# object_1.net
KiCad netlist of a schematic drawn in EAGLE
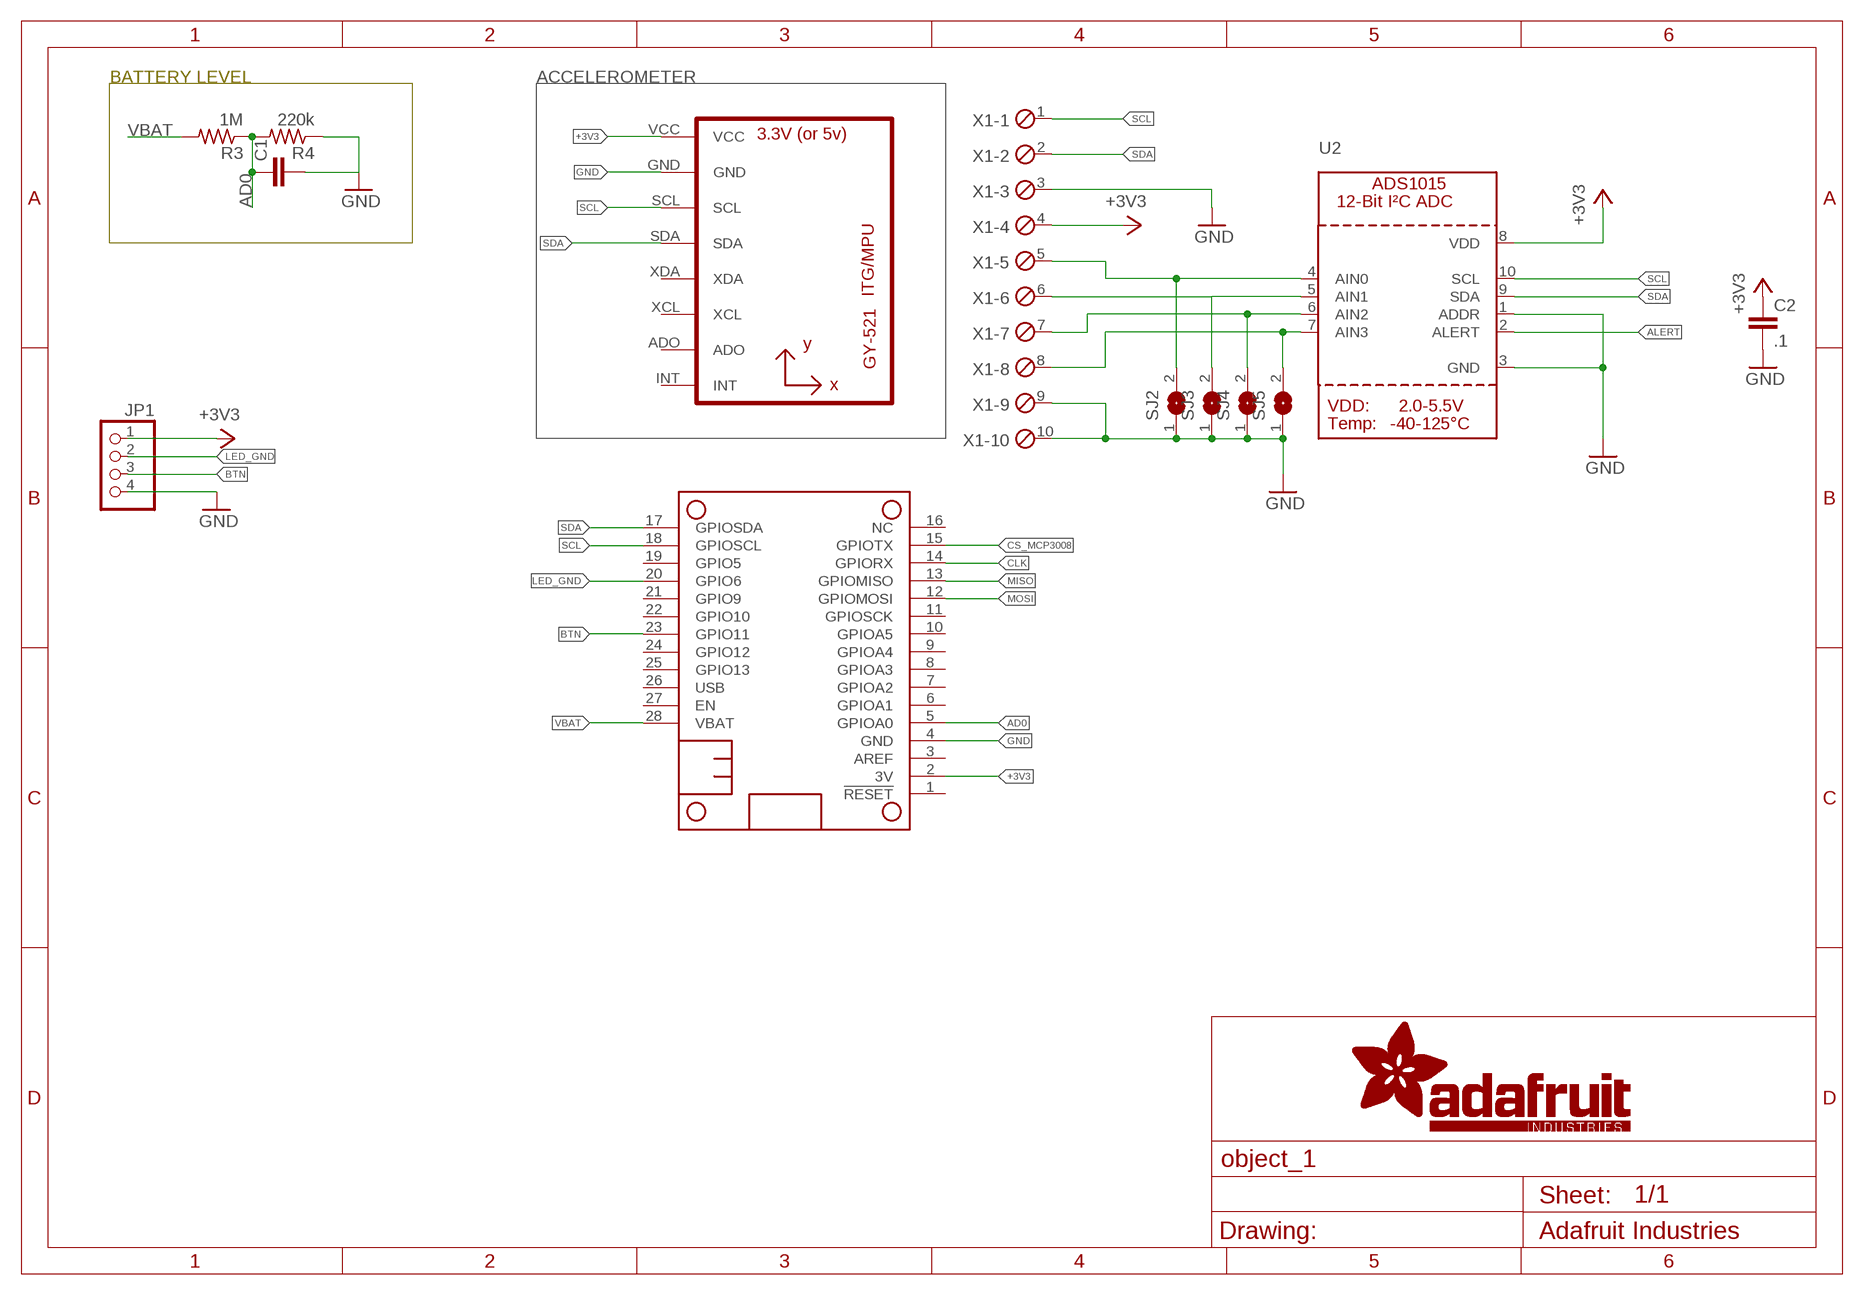
[diagram p0: schematic, sheet 1]

(export (version "E")
  (design (tool "Eeschema 10.0.6"))
  (components
    (comp (ref "C1")
      (value "C-EUC0805K")
      (footprint "eagle-import:C0805K")
      (libsource (lib "eagle-import") (part "C-EUC0805K"))
    )
    (comp (ref "C2")
      (value ".1")
      (footprint "eagle-import:C0805K")
      (libsource (lib "eagle-import") (part "C-EUC0805K"))
    )
    (comp (ref "JP1")
      (value "PINHD-1X4/90")
      (footprint "eagle-import:1X04_90")
      (libsource (lib "eagle-import") (part "PINHD-1X4/90"))
    )
    (comp (ref "MS1")
      (value "FEATHERWING_NODIM")
      (footprint "eagle-import:FEATHERWING_DIM")
      (libsource (lib "eagle-import") (part "FEATHERWING_NODIM"))
    )
    (comp (ref "R3")
      (value "1M")
      (footprint "eagle-import:M0805")
      (libsource (lib "eagle-import") (part "R-US_M0805"))
    )
    (comp (ref "R4")
      (value "220k")
      (footprint "eagle-import:M0805")
      (libsource (lib "eagle-import") (part "R-US_M0805"))
    )
    (comp (ref "SJ2")
      (value "SOLDERJUMPER")
      (footprint "eagle-import:SOLDERJUMPER_ARROW_NOPASTE")
      (libsource (lib "eagle-import") (part "SOLDERJUMPER"))
    )
    (comp (ref "SJ3")
      (value "SOLDERJUMPER")
      (footprint "eagle-import:SOLDERJUMPER_ARROW_NOPASTE")
      (libsource (lib "eagle-import") (part "SOLDERJUMPER"))
    )
    (comp (ref "SJ4")
      (value "SOLDERJUMPER")
      (footprint "eagle-import:SOLDERJUMPER_ARROW_NOPASTE")
      (libsource (lib "eagle-import") (part "SOLDERJUMPER"))
    )
    (comp (ref "SJ5")
      (value "SOLDERJUMPER")
      (footprint "eagle-import:SOLDERJUMPER_ARROW_NOPASTE")
      (libsource (lib "eagle-import") (part "SOLDERJUMPER"))
    )
    (comp (ref "U1")
      (value "GY-521MPU6050")
      (footprint "eagle-import:GY-521")
      (libsource (lib "eagle-import") (part "GY-521MPU6050"))
    )
    (comp (ref "U2")
      (value "ADC_ADS1015")
      (footprint "eagle-import:MSOP10")
      (libsource (lib "eagle-import") (part "ADC_ADS1015"))
    )
    (comp (ref "X1")
      (value "MPT10")
      (footprint "eagle-import:10POL254")
      (libsource (lib "eagle-import") (part "MPT10"))
    )
  )
  (nets
    (net (code "1") (name "+3V3") (class "Default")
      (node (ref "C2") (pin "1") (pinfunction "1_1") (pintype "passive"))
      (node (ref "JP1") (pin "1") (pinfunction "1_1") (pintype "passive"))
      (node (ref "MS1") (pin "2") (pinfunction "3V_2") (pintype "power_in"))
      (node (ref "U1") (pin "VCC") (pinfunction "VCC_VCC") (pintype "bidirectional"))
      (node (ref "U2") (pin "8") (pinfunction "VDD_8") (pintype "bidirectional"))
      (node (ref "X1") (pin "4") (pinfunction "1_4") (pintype "passive"))
    )
    (net (code "2") (name "/USB") (class "Default")
      (node (ref "MS1") (pin "26") (pinfunction "USB_26") (pintype "power_in"))
    )
    (net (code "3") (name "AD0") (class "Default")
      (node (ref "C1") (pin "1") (pinfunction "1_1") (pintype "passive"))
      (node (ref "MS1") (pin "5") (pinfunction "GPIOA0_5") (pintype "bidirectional"))
      (node (ref "R3") (pin "1") (pinfunction "1_1") (pintype "passive"))
      (node (ref "R4") (pin "2") (pinfunction "2_2") (pintype "passive"))
    )
    (net (code "4") (name "ALERT") (class "Default")
      (node (ref "U2") (pin "2") (pinfunction "ALERT_2") (pintype "bidirectional"))
    )
    (net (code "5") (name "BTN") (class "Default")
      (node (ref "JP1") (pin "3") (pinfunction "3_3") (pintype "passive"))
      (node (ref "MS1") (pin "23") (pinfunction "GPIO11_23") (pintype "bidirectional"))
    )
    (net (code "6") (name "CLK") (class "Default")
      (node (ref "MS1") (pin "14") (pinfunction "GPIORX_14") (pintype "bidirectional"))
    )
    (net (code "7") (name "CS_MCP3008") (class "Default")
      (node (ref "MS1") (pin "15") (pinfunction "GPIOTX_15") (pintype "bidirectional"))
    )
    (net (code "8") (name "GND") (class "Default")
      (node (ref "C1") (pin "2") (pinfunction "2_2") (pintype "passive"))
      (node (ref "C2") (pin "2") (pinfunction "2_2") (pintype "passive"))
      (node (ref "JP1") (pin "4") (pinfunction "4_4") (pintype "passive"))
      (node (ref "MS1") (pin "4") (pinfunction "GND_4") (pintype "power_in"))
      (node (ref "R4") (pin "1") (pinfunction "1_1") (pintype "passive"))
      (node (ref "SJ2") (pin "1") (pinfunction "1_1") (pintype "passive"))
      (node (ref "SJ3") (pin "1") (pinfunction "1_1") (pintype "passive"))
      (node (ref "SJ4") (pin "1") (pinfunction "1_1") (pintype "passive"))
      (node (ref "SJ5") (pin "1") (pinfunction "1_1") (pintype "passive"))
      (node (ref "U1") (pin "GND") (pinfunction "GND_GND") (pintype "bidirectional"))
      (node (ref "U2") (pin "1") (pinfunction "ADDR_1") (pintype "bidirectional"))
      (node (ref "U2") (pin "3") (pinfunction "GND_3") (pintype "bidirectional"))
      (node (ref "X1") (pin "10") (pinfunction "1_10") (pintype "passive"))
      (node (ref "X1") (pin "3") (pinfunction "1_3") (pintype "passive"))
      (node (ref "X1") (pin "9") (pinfunction "1_9") (pintype "passive"))
    )
    (net (code "9") (name "LED_GND") (class "Default")
      (node (ref "JP1") (pin "2") (pinfunction "2_2") (pintype "passive"))
      (node (ref "MS1") (pin "20") (pinfunction "GPIO6_20") (pintype "bidirectional"))
    )
    (net (code "10") (name "MISO") (class "Default")
      (node (ref "MS1") (pin "13") (pinfunction "GPIOMISO_13") (pintype "bidirectional"))
    )
    (net (code "11") (name "MOSI") (class "Default")
      (node (ref "MS1") (pin "12") (pinfunction "GPIOMOSI_12") (pintype "bidirectional"))
    )
    (net (code "12") (name "Net-(U2-AIN0)") (class "Default")
      (node (ref "SJ2") (pin "2") (pinfunction "2_2") (pintype "passive"))
      (node (ref "U2") (pin "4") (pinfunction "AIN0_4") (pintype "bidirectional"))
      (node (ref "X1") (pin "5") (pinfunction "1_5") (pintype "passive"))
    )
    (net (code "13") (name "Net-(U2-AIN1)") (class "Default")
      (node (ref "SJ3") (pin "2") (pinfunction "2_2") (pintype "passive"))
      (node (ref "U2") (pin "5") (pinfunction "AIN1_5") (pintype "bidirectional"))
      (node (ref "X1") (pin "6") (pinfunction "1_6") (pintype "passive"))
    )
    (net (code "14") (name "Net-(U2-AIN2)") (class "Default")
      (node (ref "SJ4") (pin "2") (pinfunction "2_2") (pintype "passive"))
      (node (ref "U2") (pin "6") (pinfunction "AIN2_6") (pintype "bidirectional"))
      (node (ref "X1") (pin "7") (pinfunction "1_7") (pintype "passive"))
    )
    (net (code "15") (name "Net-(U2-AIN3)") (class "Default")
      (node (ref "SJ5") (pin "2") (pinfunction "2_2") (pintype "passive"))
      (node (ref "U2") (pin "7") (pinfunction "AIN3_7") (pintype "bidirectional"))
      (node (ref "X1") (pin "8") (pinfunction "1_8") (pintype "passive"))
    )
    (net (code "16") (name "SCL") (class "Default")
      (node (ref "MS1") (pin "18") (pinfunction "GPIOSCL_18") (pintype "bidirectional"))
      (node (ref "U1") (pin "SCL") (pinfunction "SCL_SCL") (pintype "bidirectional"))
      (node (ref "U2") (pin "10") (pinfunction "SCL_10") (pintype "bidirectional"))
      (node (ref "X1") (pin "1") (pinfunction "1_1") (pintype "passive"))
    )
    (net (code "17") (name "SDA") (class "Default")
      (node (ref "MS1") (pin "17") (pinfunction "GPIOSDA_17") (pintype "bidirectional"))
      (node (ref "U1") (pin "SDA") (pinfunction "SDA_SDA") (pintype "bidirectional"))
      (node (ref "U2") (pin "9") (pinfunction "SDA_9") (pintype "bidirectional"))
      (node (ref "X1") (pin "2") (pinfunction "1_2") (pintype "passive"))
    )
    (net (code "18") (name "VBAT") (class "Default")
      (node (ref "MS1") (pin "28") (pinfunction "VBAT_28") (pintype "power_in"))
      (node (ref "R3") (pin "2") (pinfunction "2_2") (pintype "passive"))
    )
    (net (code "19") (name "unconnected-(MS1-AREF-Pad3)") (class "Default")
      (node (ref "MS1") (pin "3") (pinfunction "AREF_3") (pintype "passive"))
    )
    (net (code "20") (name "unconnected-(MS1-EN-Pad27)") (class "Default")
      (node (ref "MS1") (pin "27") (pinfunction "EN_27") (pintype "passive"))
    )
    (net (code "21") (name "unconnected-(MS1-GPIO5-Pad19)") (class "Default")
      (node (ref "MS1") (pin "19") (pinfunction "GPIO5_19") (pintype "bidirectional"))
    )
    (net (code "22") (name "unconnected-(MS1-GPIO9-Pad21)") (class "Default")
      (node (ref "MS1") (pin "21") (pinfunction "GPIO9_21") (pintype "bidirectional"))
    )
    (net (code "23") (name "unconnected-(MS1-GPIO10-Pad22)") (class "Default")
      (node (ref "MS1") (pin "22") (pinfunction "GPIO10_22") (pintype "bidirectional"))
    )
    (net (code "24") (name "unconnected-(MS1-GPIO12-Pad24)") (class "Default")
      (node (ref "MS1") (pin "24") (pinfunction "GPIO12_24") (pintype "bidirectional"))
    )
    (net (code "25") (name "unconnected-(MS1-GPIO13-Pad25)") (class "Default")
      (node (ref "MS1") (pin "25") (pinfunction "GPIO13_25") (pintype "bidirectional"))
    )
    (net (code "26") (name "unconnected-(MS1-GPIOA1-Pad6)") (class "Default")
      (node (ref "MS1") (pin "6") (pinfunction "GPIOA1_6") (pintype "bidirectional"))
    )
    (net (code "27") (name "unconnected-(MS1-GPIOA2-Pad7)") (class "Default")
      (node (ref "MS1") (pin "7") (pinfunction "GPIOA2_7") (pintype "bidirectional"))
    )
    (net (code "28") (name "unconnected-(MS1-GPIOA3-Pad8)") (class "Default")
      (node (ref "MS1") (pin "8") (pinfunction "GPIOA3_8") (pintype "bidirectional"))
    )
    (net (code "29") (name "unconnected-(MS1-GPIOA4-Pad9)") (class "Default")
      (node (ref "MS1") (pin "9") (pinfunction "GPIOA4_9") (pintype "bidirectional"))
    )
    (net (code "30") (name "unconnected-(MS1-GPIOA5-Pad10)") (class "Default")
      (node (ref "MS1") (pin "10") (pinfunction "GPIOA5_10") (pintype "bidirectional"))
    )
    (net (code "31") (name "unconnected-(MS1-GPIOSCK-Pad11)") (class "Default")
      (node (ref "MS1") (pin "11") (pinfunction "GPIOSCK_11") (pintype "bidirectional"))
    )
    (net (code "32") (name "unconnected-(MS1-NC-Pad16)") (class "Default")
      (node (ref "MS1") (pin "16") (pinfunction "NC_16") (pintype "passive"))
    )
    (net (code "33") (name "unconnected-(MS1-~{RESET}-Pad1)") (class "Default")
      (node (ref "MS1") (pin "1") (pinfunction "~{RESET}_1") (pintype "input"))
    )
    (net (code "34") (name "unconnected-(U1-PadADO)") (class "Default")
      (node (ref "U1") (pin "ADO") (pinfunction "ADO_ADO") (pintype "bidirectional"))
    )
    (net (code "35") (name "unconnected-(U1-PadINT)") (class "Default")
      (node (ref "U1") (pin "INT") (pinfunction "INT_INT") (pintype "bidirectional"))
    )
    (net (code "36") (name "unconnected-(U1-PadXCL)") (class "Default")
      (node (ref "U1") (pin "XCL") (pinfunction "XCL_XCL") (pintype "bidirectional"))
    )
    (net (code "37") (name "unconnected-(U1-PadXDA)") (class "Default")
      (node (ref "U1") (pin "XDA") (pinfunction "XDA_XDA") (pintype "bidirectional"))
    )
  )
)
